# DDR3_ZET6.net
KiCad netlist of a schematic drawn in Altium Designer
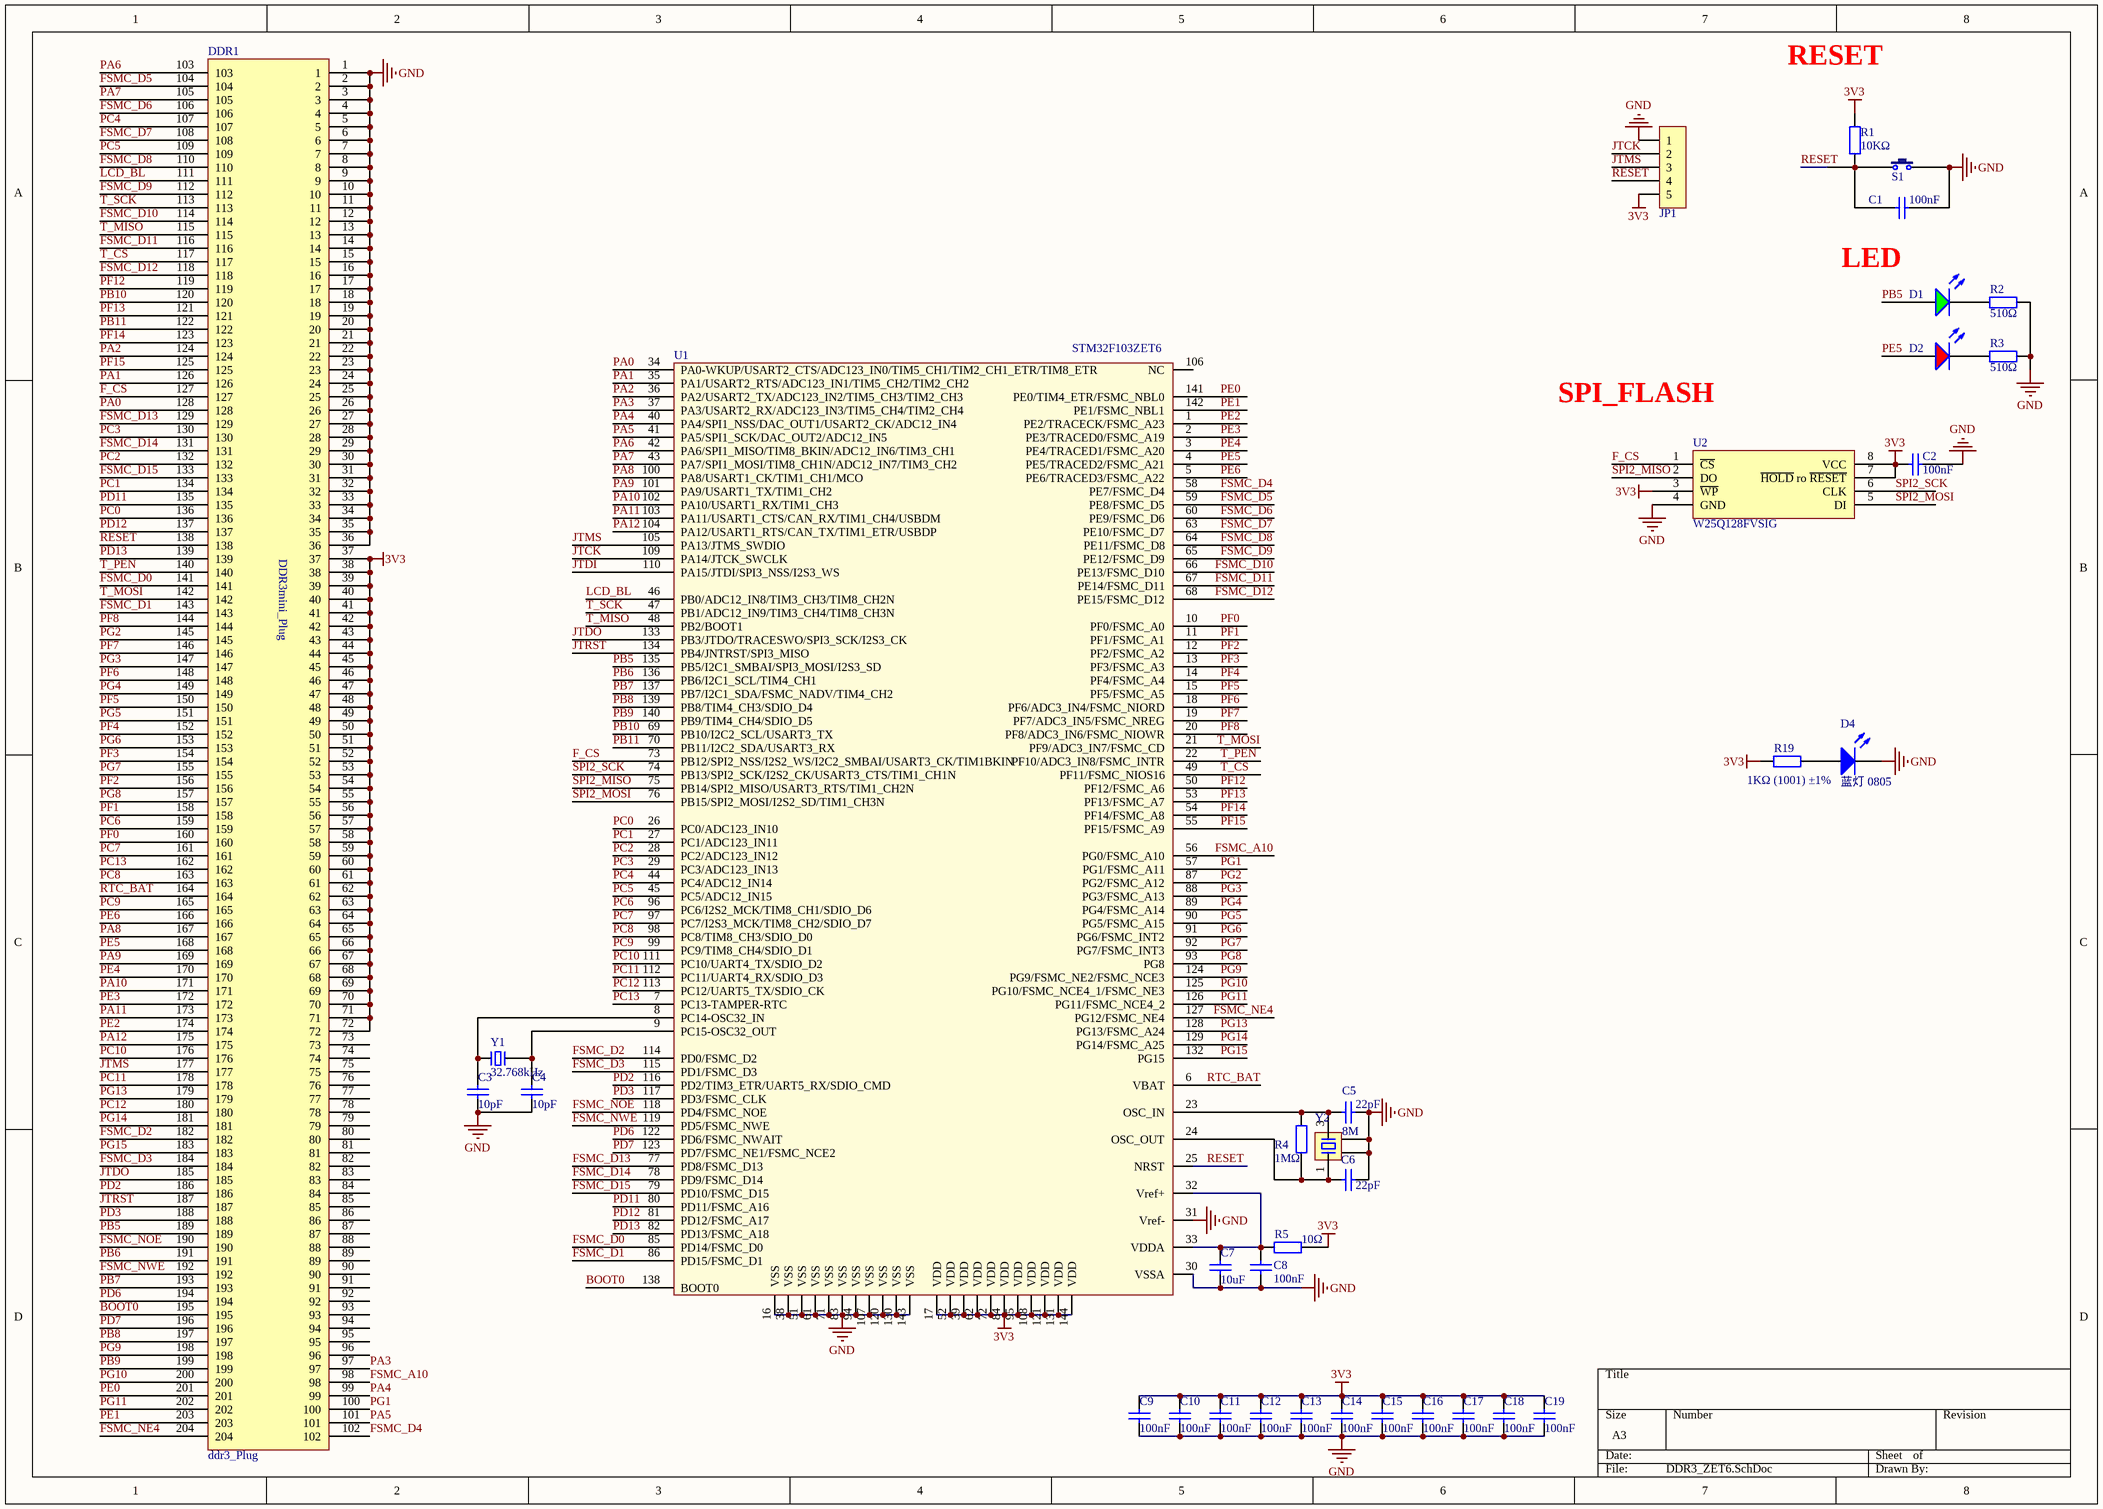
[diagram p0: DDR3_ZET6.SchDoc]

(export (version "E")
  (design (tool "Eeschema 10.0.6"))
  (components
    (comp (ref "C1")
      (value "100nF")
      (footprint "LC-0805_C")
      (description "贴片电容")
      (libsource (lib "Miscellaneous Devices LC") (part "0805 100nF(104) 10% 50V"))
    )
    (comp (ref "C2")
      (value "100nF")
      (footprint "LC-0805_C")
      (description "贴片电容")
      (libsource (lib "Miscellaneous Devices LC") (part "0805 100nF(104) 10% 50V"))
    )
    (comp (ref "C3")
      (value "10pF")
      (footprint "LC-0805_C")
      (description "贴片电容")
      (libsource (lib "Miscellaneous Devices LC") (part "0805 10pF (100) 5% 50V"))
    )
    (comp (ref "C4")
      (value "10pF")
      (footprint "LC-0805_C")
      (description "贴片电容")
      (libsource (lib "Miscellaneous Devices LC") (part "0805 10pF (100) 5% 50V"))
    )
    (comp (ref "C5")
      (value "22pF")
      (footprint "LC-0805_C")
      (description "贴片电容")
      (libsource (lib "Miscellaneous Devices LC") (part "0805 22pF (220) 5% 50V"))
    )
    (comp (ref "C6")
      (value "22pF")
      (footprint "LC-0805_C")
      (description "贴片电容")
      (libsource (lib "Miscellaneous Devices LC") (part "0805 22pF (220) 5% 50V"))
    )
    (comp (ref "C7")
      (value "10uF")
      (footprint "LC-0805_C")
      (description "贴片电容")
      (libsource (lib "Miscellaneous Devices LC") (part "0805 10uF (106) 10% 25V"))
    )
    (comp (ref "C8")
      (value "100nF")
      (footprint "LC-0805_C")
      (description "贴片电容")
      (libsource (lib "Miscellaneous Devices LC") (part "0805 100nF(104) 10% 50V"))
    )
    (comp (ref "C9")
      (value "100nF")
      (footprint "LC-0805_C")
      (description "贴片电容")
      (libsource (lib "Miscellaneous Devices LC") (part "0805 100nF(104) 10% 50V"))
    )
    (comp (ref "C10")
      (value "100nF")
      (footprint "LC-0805_C")
      (description "贴片电容")
      (libsource (lib "Miscellaneous Devices LC") (part "0805 100nF(104) 10% 50V"))
    )
    (comp (ref "C11")
      (value "100nF")
      (footprint "LC-0805_C")
      (description "贴片电容")
      (libsource (lib "Miscellaneous Devices LC") (part "0805 100nF(104) 10% 50V"))
    )
    (comp (ref "C12")
      (value "100nF")
      (footprint "LC-0805_C")
      (description "贴片电容")
      (libsource (lib "Miscellaneous Devices LC") (part "0805 100nF(104) 10% 50V"))
    )
    (comp (ref "C13")
      (value "100nF")
      (footprint "LC-0805_C")
      (description "贴片电容")
      (libsource (lib "Miscellaneous Devices LC") (part "0805 100nF(104) 10% 50V"))
    )
    (comp (ref "C14")
      (value "100nF")
      (footprint "LC-0805_C")
      (description "贴片电容")
      (libsource (lib "Miscellaneous Devices LC") (part "0805 100nF(104) 10% 50V"))
    )
    (comp (ref "C15")
      (value "100nF")
      (footprint "LC-0805_C")
      (description "贴片电容")
      (libsource (lib "Miscellaneous Devices LC") (part "0805 100nF(104) 10% 50V"))
    )
    (comp (ref "C16")
      (value "100nF")
      (footprint "LC-0805_C")
      (description "贴片电容")
      (libsource (lib "Miscellaneous Devices LC") (part "0805 100nF(104) 10% 50V"))
    )
    (comp (ref "C17")
      (value "100nF")
      (footprint "LC-0805_C")
      (description "贴片电容")
      (libsource (lib "Miscellaneous Devices LC") (part "0805 100nF(104) 10% 50V"))
    )
    (comp (ref "C18")
      (value "100nF")
      (footprint "LC-0805_C")
      (description "贴片电容")
      (libsource (lib "Miscellaneous Devices LC") (part "0805 100nF(104) 10% 50V"))
    )
    (comp (ref "C19")
      (value "100nF")
      (footprint "LC-0805_C")
      (description "贴片电容")
      (libsource (lib "Miscellaneous Devices LC") (part "0805 100nF(104) 10% 50V"))
    )
    (comp (ref "D1")
      (value "翠绿 0805")
      (footprint "LC-0805_LED_S1")
      (description "发光二极管")
      (libsource (lib "Miscellaneous Devices LC") (part "0805 翠绿"))
    )
    (comp (ref "D2")
      (value "红灯 0805")
      (footprint "LC-0805_LED_S1")
      (description "发光二极管")
      (libsource (lib "Miscellaneous Devices LC") (part "0805 红灯"))
    )
    (comp (ref "D4")
      (value "蓝灯 0805")
      (footprint "LC-0805_LED_S1")
      (description "发光二极管")
      (libsource (lib "Miscellaneous Devices LC") (part "0805 蓝灯"))
    )
    (comp (ref "DDR1")
      (value "ddr3_Plug")
      (footprint "DDR3_PLUG_LTE")
      (libsource (lib "my_lib") (part "ddr3_Plug"))
    )
    (comp (ref "JP1")
      (value "HDR-1X5")
      (footprint "HDR-1X5")
      (description "5P接插件")
      (fields (field (name "版权归属") "黎明电子style"))
      (libsource (lib "接插件") (part "Header 5"))
    )
    (comp (ref "R1")
      (value "10KΩ")
      (footprint "LC-0805_R")
      (description "贴片电阻")
      (libsource (lib "Miscellaneous Devices LC") (part "0805 10KΩ (1002) 1%"))
    )
    (comp (ref "R2")
      (value "510Ω")
      (footprint "LC-0805_R")
      (description "贴片电阻")
      (libsource (lib "Miscellaneous Devices LC") (part "0805 510Ω (5100) 1%"))
    )
    (comp (ref "R3")
      (value "510Ω")
      (footprint "LC-0805_R")
      (description "贴片电阻")
      (libsource (lib "Miscellaneous Devices LC") (part "0805 510Ω (5100) 1%"))
    )
    (comp (ref "R4")
      (value "1MΩ")
      (footprint "LC-0805_R")
      (description "贴片电阻")
      (libsource (lib "Miscellaneous Devices LC") (part "0805 1MΩ (1004) 1%"))
    )
    (comp (ref "R5")
      (value "10Ω")
      (footprint "LC-0805_R")
      (description "贴片电阻")
      (libsource (lib "Miscellaneous Devices LC") (part "0805 10Ω (10R0) 1%"))
    )
    (comp (ref "R19")
      (value "1KΩ (1001) ±1%")
      (footprint "LC-0805_R")
      (description "贴片电阻")
      (libsource (lib "Miscellaneous Devices LC") (part "0805 1KΩ (1001) 1%"))
    )
    (comp (ref "S1")
      (value "RESET")
      (footprint "TSW SMD-3*6*2.5")
      (description "3x6轻触开关")
      (fields (field (name "版权归属") "黎明电子style"))
      (libsource (lib "按键-开关") (part "TSW 3x6"))
    )
    (comp (ref "U1")
      (value "STM32F103ZET6")
      (footprint "LC-LQFP-144_20x20x05P")
      (libsource (lib "WarShip V3 STM32103封装库") (part "STM32F103ZET6"))
    )
    (comp (ref "U2")
      (value "W25Q128FVSIG")
      (footprint "LC-SOIC-8_208mil")
      (description "Flash ROM")
      (libsource (lib "Miscellaneous Devices LC") (part "W25Q128FVSIG"))
    )
    (comp (ref "Y1")
      (value "32.768kHz")
      (footprint "XTAL-3215")
      (description "2脚晶振")
      (fields (field (name "版权归属") "黎明电子style"))
      (libsource (lib "保险丝-晶振") (part "XTAL-2"))
    )
    (comp (ref "Y2")
      (value "8M")
      (footprint "XTAL-3225")
      (description "4脚晶振")
      (fields (field (name "版权归属") "黎明电子style"))
      (libsource (lib "保险丝-晶振") (part "XTAL-4"))
    )
  )
  (nets
    (net (code "1") (name "/BOOT0") (class "Default")
      (node (ref "DDR1") (pin "195") (pinfunction "195_195") (pintype "passive"))
      (node (ref "U1") (pin "138") (pinfunction "BOOT0_138") (pintype "passive"))
    )
    (net (code "2") (name "/FSMC_A10") (class "Default")
      (node (ref "DDR1") (pin "98") (pinfunction "98_98") (pintype "passive"))
      (node (ref "U1") (pin "56") (pinfunction "PG0/FSMC_A10_56") (pintype "passive"))
    )
    (net (code "3") (name "/FSMC_D0") (class "Default")
      (node (ref "DDR1") (pin "141") (pinfunction "141_141") (pintype "passive"))
      (node (ref "U1") (pin "85") (pinfunction "PD14/FSMC_D0_85") (pintype "passive"))
    )
    (net (code "4") (name "/FSMC_D1") (class "Default")
      (node (ref "DDR1") (pin "143") (pinfunction "143_143") (pintype "passive"))
      (node (ref "U1") (pin "86") (pinfunction "PD15/FSMC_D1_86") (pintype "passive"))
    )
    (net (code "5") (name "/FSMC_D2") (class "Default")
      (node (ref "DDR1") (pin "182") (pinfunction "182_182") (pintype "passive"))
      (node (ref "U1") (pin "114") (pinfunction "PD0/FSMC_D2_114") (pintype "passive"))
    )
    (net (code "6") (name "/FSMC_D3") (class "Default")
      (node (ref "DDR1") (pin "184") (pinfunction "184_184") (pintype "passive"))
      (node (ref "U1") (pin "115") (pinfunction "PD1/FSMC_D3_115") (pintype "passive"))
    )
    (net (code "7") (name "/FSMC_D4") (class "Default")
      (node (ref "DDR1") (pin "102") (pinfunction "102_102") (pintype "passive"))
      (node (ref "U1") (pin "58") (pinfunction "PE7/FSMC_D4_58") (pintype "passive"))
    )
    (net (code "8") (name "/FSMC_D5") (class "Default")
      (node (ref "DDR1") (pin "104") (pinfunction "104_104") (pintype "passive"))
      (node (ref "U1") (pin "59") (pinfunction "PE8/FSMC_D5_59") (pintype "passive"))
    )
    (net (code "9") (name "/FSMC_D6") (class "Default")
      (node (ref "DDR1") (pin "106") (pinfunction "106_106") (pintype "passive"))
      (node (ref "U1") (pin "60") (pinfunction "PE9/FSMC_D6_60") (pintype "passive"))
    )
    (net (code "10") (name "/FSMC_D7") (class "Default")
      (node (ref "DDR1") (pin "108") (pinfunction "108_108") (pintype "passive"))
      (node (ref "U1") (pin "63") (pinfunction "PE10/FSMC_D7_63") (pintype "passive"))
    )
    (net (code "11") (name "/FSMC_D8") (class "Default")
      (node (ref "DDR1") (pin "110") (pinfunction "110_110") (pintype "passive"))
      (node (ref "U1") (pin "64") (pinfunction "PE11/FSMC_D8_64") (pintype "passive"))
    )
    (net (code "12") (name "/FSMC_D9") (class "Default")
      (node (ref "DDR1") (pin "112") (pinfunction "112_112") (pintype "passive"))
      (node (ref "U1") (pin "65") (pinfunction "PE12/FSMC_D9_65") (pintype "passive"))
    )
    (net (code "13") (name "/FSMC_D10") (class "Default")
      (node (ref "DDR1") (pin "114") (pinfunction "114_114") (pintype "passive"))
      (node (ref "U1") (pin "66") (pinfunction "PE13/FSMC_D10_66") (pintype "passive"))
    )
    (net (code "14") (name "/FSMC_D11") (class "Default")
      (node (ref "DDR1") (pin "116") (pinfunction "116_116") (pintype "passive"))
      (node (ref "U1") (pin "67") (pinfunction "PE14/FSMC_D11_67") (pintype "passive"))
    )
    (net (code "15") (name "/FSMC_D12") (class "Default")
      (node (ref "DDR1") (pin "118") (pinfunction "118_118") (pintype "passive"))
      (node (ref "U1") (pin "68") (pinfunction "PE15/FSMC_D12_68") (pintype "passive"))
    )
    (net (code "16") (name "/FSMC_D13") (class "Default")
      (node (ref "DDR1") (pin "129") (pinfunction "129_129") (pintype "passive"))
      (node (ref "U1") (pin "77") (pinfunction "PD8/FSMC_D13_77") (pintype "passive"))
    )
    (net (code "17") (name "/FSMC_D14") (class "Default")
      (node (ref "DDR1") (pin "131") (pinfunction "131_131") (pintype "passive"))
      (node (ref "U1") (pin "78") (pinfunction "PD9/FSMC_D14_78") (pintype "passive"))
    )
    (net (code "18") (name "/FSMC_D15") (class "Default")
      (node (ref "DDR1") (pin "133") (pinfunction "133_133") (pintype "passive"))
      (node (ref "U1") (pin "79") (pinfunction "PD10/FSMC_D15_79") (pintype "passive"))
    )
    (net (code "19") (name "/FSMC_NE4") (class "Default")
      (node (ref "DDR1") (pin "204") (pinfunction "204_204") (pintype "passive"))
      (node (ref "U1") (pin "127") (pinfunction "PG12/FSMC_NE4_127") (pintype "passive"))
    )
    (net (code "20") (name "/FSMC_NOE") (class "Default")
      (node (ref "DDR1") (pin "190") (pinfunction "190_190") (pintype "passive"))
      (node (ref "U1") (pin "118") (pinfunction "PD4/FSMC_NOE_118") (pintype "passive"))
    )
    (net (code "21") (name "/FSMC_NWE") (class "Default")
      (node (ref "DDR1") (pin "192") (pinfunction "192_192") (pintype "passive"))
      (node (ref "U1") (pin "119") (pinfunction "PD5/FSMC_NWE_119") (pintype "passive"))
    )
    (net (code "22") (name "/F_CS") (class "Default")
      (node (ref "DDR1") (pin "127") (pinfunction "127_127") (pintype "passive"))
      (node (ref "U1") (pin "73") (pinfunction "PB12/SPI2_NSS/I2S2_WS/I2C2_SMBAI/USART3_CK/TIM1BKIN_73") (pintype "passive"))
      (node (ref "U2") (pin "1") (pinfunction "~{CS}_1") (pintype "passive"))
    )
    (net (code "23") (name "/JTCK") (class "Default")
      (node (ref "JP1") (pin "2") (pinfunction "2_2") (pintype "passive"))
      (node (ref "U1") (pin "109") (pinfunction "PA14/JTCK_SWCLK_109") (pintype "passive"))
    )
    (net (code "24") (name "/JTDI") (class "Default")
      (node (ref "U1") (pin "110") (pinfunction "PA15/JTDI/SPI3_NSS/I2S3_WS_110") (pintype "passive"))
    )
    (net (code "25") (name "/JTDO") (class "Default")
      (node (ref "DDR1") (pin "185") (pinfunction "185_185") (pintype "passive"))
      (node (ref "U1") (pin "133") (pinfunction "PB3/JTDO/TRACESWO/SPI3_SCK/I2S3_CK_133") (pintype "passive"))
    )
    (net (code "26") (name "/JTMS") (class "Default")
      (node (ref "DDR1") (pin "177") (pinfunction "177_177") (pintype "passive"))
      (node (ref "JP1") (pin "3") (pinfunction "3_3") (pintype "passive"))
      (node (ref "U1") (pin "105") (pinfunction "PA13/JTMS_SWDIO_105") (pintype "passive"))
    )
    (net (code "27") (name "/JTRST") (class "Default")
      (node (ref "DDR1") (pin "187") (pinfunction "187_187") (pintype "passive"))
      (node (ref "U1") (pin "134") (pinfunction "PB4/JNTRST/SPI3_MISO_134") (pintype "passive"))
    )
    (net (code "28") (name "/LCD_BL") (class "Default")
      (node (ref "DDR1") (pin "111") (pinfunction "111_111") (pintype "passive"))
      (node (ref "U1") (pin "46") (pinfunction "PB0/ADC12_IN8/TIM3_CH3/TIM8_CH2N_46") (pintype "passive"))
    )
    (net (code "29") (name "/PA0") (class "Default")
      (node (ref "DDR1") (pin "128") (pinfunction "128_128") (pintype "passive"))
      (node (ref "U1") (pin "34") (pinfunction "PA0-WKUP/USART2_CTS/ADC123_IN0/TIM5_CH1/TIM2_CH1_ETR/TIM8_ETR_34") (pintype "passive"))
    )
    (net (code "30") (name "/PA1") (class "Default")
      (node (ref "DDR1") (pin "126") (pinfunction "126_126") (pintype "passive"))
      (node (ref "U1") (pin "35") (pinfunction "PA1/USART2_RTS/ADC123_IN1/TIM5_CH2/TIM2_CH2_35") (pintype "passive"))
    )
    (net (code "31") (name "/PA2") (class "Default")
      (node (ref "DDR1") (pin "124") (pinfunction "124_124") (pintype "passive"))
      (node (ref "U1") (pin "36") (pinfunction "PA2/USART2_TX/ADC123_IN2/TIM5_CH3/TIM2_CH3_36") (pintype "passive"))
    )
    (net (code "32") (name "/PA3") (class "Default")
      (node (ref "DDR1") (pin "97") (pinfunction "97_97") (pintype "passive"))
      (node (ref "U1") (pin "37") (pinfunction "PA3/USART2_RX/ADC123_IN3/TIM5_CH4/TIM2_CH4_37") (pintype "passive"))
    )
    (net (code "33") (name "/PA4") (class "Default")
      (node (ref "DDR1") (pin "99") (pinfunction "99_99") (pintype "passive"))
      (node (ref "U1") (pin "40") (pinfunction "PA4/SPI1_NSS/DAC_OUT1/USART2_CK/ADC12_IN4_40") (pintype "passive"))
    )
    (net (code "34") (name "/PA5") (class "Default")
      (node (ref "DDR1") (pin "101") (pinfunction "101_101") (pintype "passive"))
      (node (ref "U1") (pin "41") (pinfunction "PA5/SPI1_SCK/DAC_OUT2/ADC12_IN5_41") (pintype "passive"))
    )
    (net (code "35") (name "/PA6") (class "Default")
      (node (ref "DDR1") (pin "103") (pinfunction "103_103") (pintype "passive"))
      (node (ref "U1") (pin "42") (pinfunction "PA6/SPI1_MISO/TIM8_BKIN/ADC12_IN6/TIM3_CH1_42") (pintype "passive"))
    )
    (net (code "36") (name "/PA7") (class "Default")
      (node (ref "DDR1") (pin "105") (pinfunction "105_105") (pintype "passive"))
      (node (ref "U1") (pin "43") (pinfunction "PA7/SPI1_MOSI/TIM8_CH1N/ADC12_IN7/TIM3_CH2_43") (pintype "passive"))
    )
    (net (code "37") (name "/PA8") (class "Default")
      (node (ref "DDR1") (pin "167") (pinfunction "167_167") (pintype "passive"))
      (node (ref "U1") (pin "100") (pinfunction "PA8/USART1_CK/TIM1_CH1/MCO_100") (pintype "passive"))
    )
    (net (code "38") (name "/PA9") (class "Default")
      (node (ref "DDR1") (pin "169") (pinfunction "169_169") (pintype "passive"))
      (node (ref "U1") (pin "101") (pinfunction "PA9/USART1_TX/TIM1_CH2_101") (pintype "passive"))
    )
    (net (code "39") (name "/PA10") (class "Default")
      (node (ref "DDR1") (pin "171") (pinfunction "171_171") (pintype "passive"))
      (node (ref "U1") (pin "102") (pinfunction "PA10/USART1_RX/TIM1_CH3_102") (pintype "passive"))
    )
    (net (code "40") (name "/PA11") (class "Default")
      (node (ref "DDR1") (pin "173") (pinfunction "173_173") (pintype "passive"))
      (node (ref "U1") (pin "103") (pinfunction "PA11/USART1_CTS/CAN_RX/TIM1_CH4/USBDM_103") (pintype "passive"))
    )
    (net (code "41") (name "/PA12") (class "Default")
      (node (ref "DDR1") (pin "175") (pinfunction "175_175") (pintype "passive"))
      (node (ref "U1") (pin "104") (pinfunction "PA12/USART1_RTS/CAN_TX/TIM1_ETR/USBDP_104") (pintype "passive"))
    )
    (net (code "42") (name "/PB5") (class "Default")
      (node (ref "D1") (pin "A") (pinfunction "A_A") (pintype "passive"))
      (node (ref "DDR1") (pin "189") (pinfunction "189_189") (pintype "passive"))
      (node (ref "U1") (pin "135") (pinfunction "PB5/I2C1_SMBAI/SPI3_MOSI/I2S3_SD_135") (pintype "passive"))
    )
    (net (code "43") (name "/PB6") (class "Default")
      (node (ref "DDR1") (pin "191") (pinfunction "191_191") (pintype "passive"))
      (node (ref "U1") (pin "136") (pinfunction "PB6/I2C1_SCL/TIM4_CH1_136") (pintype "passive"))
    )
    (net (code "44") (name "/PB7") (class "Default")
      (node (ref "DDR1") (pin "193") (pinfunction "193_193") (pintype "passive"))
      (node (ref "U1") (pin "137") (pinfunction "PB7/I2C1_SDA/FSMC_NADV/TIM4_CH2_137") (pintype "passive"))
    )
    (net (code "45") (name "/PB8") (class "Default")
      (node (ref "DDR1") (pin "197") (pinfunction "197_197") (pintype "passive"))
      (node (ref "U1") (pin "139") (pinfunction "PB8/TIM4_CH3/SDIO_D4_139") (pintype "passive"))
    )
    (net (code "46") (name "/PB9") (class "Default")
      (node (ref "DDR1") (pin "199") (pinfunction "199_199") (pintype "passive"))
      (node (ref "U1") (pin "140") (pinfunction "PB9/TIM4_CH4/SDIO_D5_140") (pintype "passive"))
    )
    (net (code "47") (name "/PB10") (class "Default")
      (node (ref "DDR1") (pin "120") (pinfunction "120_120") (pintype "passive"))
      (node (ref "U1") (pin "69") (pinfunction "PB10/I2C2_SCL/USART3_TX_69") (pintype "passive"))
    )
    (net (code "48") (name "/PB11") (class "Default")
      (node (ref "DDR1") (pin "122") (pinfunction "122_122") (pintype "passive"))
      (node (ref "U1") (pin "70") (pinfunction "PB11/I2C2_SDA/USART3_RX_70") (pintype "passive"))
    )
    (net (code "49") (name "/PC0") (class "Default")
      (node (ref "DDR1") (pin "136") (pinfunction "136_136") (pintype "passive"))
      (node (ref "U1") (pin "26") (pinfunction "PC0/ADC123_IN10_26") (pintype "passive"))
    )
    (net (code "50") (name "/PC1") (class "Default")
      (node (ref "DDR1") (pin "134") (pinfunction "134_134") (pintype "passive"))
      (node (ref "U1") (pin "27") (pinfunction "PC1/ADC123_IN11_27") (pintype "passive"))
    )
    (net (code "51") (name "/PC2") (class "Default")
      (node (ref "DDR1") (pin "132") (pinfunction "132_132") (pintype "passive"))
      (node (ref "U1") (pin "28") (pinfunction "PC2/ADC123_IN12_28") (pintype "passive"))
    )
    (net (code "52") (name "/PC3") (class "Default")
      (node (ref "DDR1") (pin "130") (pinfunction "130_130") (pintype "passive"))
      (node (ref "U1") (pin "29") (pinfunction "PC3/ADC123_IN13_29") (pintype "passive"))
    )
    (net (code "53") (name "/PC4") (class "Default")
      (node (ref "DDR1") (pin "107") (pinfunction "107_107") (pintype "passive"))
      (node (ref "U1") (pin "44") (pinfunction "PC4/ADC12_IN14_44") (pintype "passive"))
    )
    (net (code "54") (name "/PC5") (class "Default")
      (node (ref "DDR1") (pin "109") (pinfunction "109_109") (pintype "passive"))
      (node (ref "U1") (pin "45") (pinfunction "PC5/ADC12_IN15_45") (pintype "passive"))
    )
    (net (code "55") (name "/PC6") (class "Default")
      (node (ref "DDR1") (pin "159") (pinfunction "159_159") (pintype "passive"))
      (node (ref "U1") (pin "96") (pinfunction "PC6/I2S2_MCK/TIM8_CH1/SDIO_D6_96") (pintype "passive"))
    )
    (net (code "56") (name "/PC7") (class "Default")
      (node (ref "DDR1") (pin "161") (pinfunction "161_161") (pintype "passive"))
      (node (ref "U1") (pin "97") (pinfunction "PC7/I2S3_MCK/TIM8_CH2/SDIO_D7_97") (pintype "passive"))
    )
    (net (code "57") (name "/PC8") (class "Default")
      (node (ref "DDR1") (pin "163") (pinfunction "163_163") (pintype "passive"))
      (node (ref "U1") (pin "98") (pinfunction "PC8/TIM8_CH3/SDIO_D0_98") (pintype "passive"))
    )
    (net (code "58") (name "/PC9") (class "Default")
      (node (ref "DDR1") (pin "165") (pinfunction "165_165") (pintype "passive"))
      (node (ref "U1") (pin "99") (pinfunction "PC9/TIM8_CH4/SDIO_D1_99") (pintype "passive"))
    )
    (net (code "59") (name "/PC10") (class "Default")
      (node (ref "DDR1") (pin "176") (pinfunction "176_176") (pintype "passive"))
      (node (ref "U1") (pin "111") (pinfunction "PC10/UART4_TX/SDIO_D2_111") (pintype "passive"))
    )
    (net (code "60") (name "/PC11") (class "Default")
      (node (ref "DDR1") (pin "178") (pinfunction "178_178") (pintype "passive"))
      (node (ref "U1") (pin "112") (pinfunction "PC11/UART4_RX/SDIO_D3_112") (pintype "passive"))
    )
    (net (code "61") (name "/PC12") (class "Default")
      (node (ref "DDR1") (pin "180") (pinfunction "180_180") (pintype "passive"))
      (node (ref "U1") (pin "113") (pinfunction "PC12/UART5_TX/SDIO_CK_113") (pintype "passive"))
    )
    (net (code "62") (name "/PC13") (class "Default")
      (node (ref "DDR1") (pin "162") (pinfunction "162_162") (pintype "passive"))
      (node (ref "U1") (pin "7") (pinfunction "PC13-TAMPER-RTC_7") (pintype "passive"))
    )
    (net (code "63") (name "/PD2") (class "Default")
      (node (ref "DDR1") (pin "186") (pinfunction "186_186") (pintype "passive"))
      (node (ref "U1") (pin "116") (pinfunction "PD2/TIM3_ETR/UART5_RX/SDIO_CMD_116") (pintype "passive"))
    )
    (net (code "64") (name "/PD3") (class "Default")
      (node (ref "DDR1") (pin "188") (pinfunction "188_188") (pintype "passive"))
      (node (ref "U1") (pin "117") (pinfunction "PD3/FSMC_CLK_117") (pintype "passive"))
    )
    (net (code "65") (name "/PD6") (class "Default")
      (node (ref "DDR1") (pin "194") (pinfunction "194_194") (pintype "passive"))
      (node (ref "U1") (pin "122") (pinfunction "PD6/FSMC_NWAIT_122") (pintype "passive"))
    )
    (net (code "66") (name "/PD7") (class "Default")
      (node (ref "DDR1") (pin "196") (pinfunction "196_196") (pintype "passive"))
      (node (ref "U1") (pin "123") (pinfunction "PD7/FSMC_NE1/FSMC_NCE2_123") (pintype "passive"))
    )
    (net (code "67") (name "/PD11") (class "Default")
      (node (ref "DDR1") (pin "135") (pinfunction "135_135") (pintype "passive"))
      (node (ref "U1") (pin "80") (pinfunction "PD11/FSMC_A16_80") (pintype "passive"))
    )
    (net (code "68") (name "/PD12") (class "Default")
      (node (ref "DDR1") (pin "137") (pinfunction "137_137") (pintype "passive"))
      (node (ref "U1") (pin "81") (pinfunction "PD12/FSMC_A17_81") (pintype "passive"))
    )
    (net (code "69") (name "/PD13") (class "Default")
      (node (ref "DDR1") (pin "139") (pinfunction "139_139") (pintype "passive"))
      (node (ref "U1") (pin "82") (pinfunction "PD13/FSMC_A18_82") (pintype "passive"))
    )
    (net (code "70") (name "/PE0") (class "Default")
      (node (ref "DDR1") (pin "201") (pinfunction "201_201") (pintype "passive"))
      (node (ref "U1") (pin "141") (pinfunction "PE0/TIM4_ETR/FSMC_NBL0_141") (pintype "passive"))
    )
    (net (code "71") (name "/PE1") (class "Default")
      (node (ref "DDR1") (pin "203") (pinfunction "203_203") (pintype "passive"))
      (node (ref "U1") (pin "142") (pinfunction "PE1/FSMC_NBL1_142") (pintype "passive"))
    )
    (net (code "72") (name "/PE2") (class "Default")
      (node (ref "DDR1") (pin "174") (pinfunction "174_174") (pintype "passive"))
      (node (ref "U1") (pin "1") (pinfunction "PE2/TRACECK/FSMC_A23_1") (pintype "passive"))
    )
    (net (code "73") (name "/PE3") (class "Default")
      (node (ref "DDR1") (pin "172") (pinfunction "172_172") (pintype "passive"))
      (node (ref "U1") (pin "2") (pinfunction "PE3/TRACED0/FSMC_A19_2") (pintype "passive"))
    )
    (net (code "74") (name "/PE4") (class "Default")
      (node (ref "DDR1") (pin "170") (pinfunction "170_170") (pintype "passive"))
      (node (ref "U1") (pin "3") (pinfunction "PE4/TRACED1/FSMC_A20_3") (pintype "passive"))
    )
    (net (code "75") (name "/PE5") (class "Default")
      (node (ref "D2") (pin "A") (pinfunction "A_A") (pintype "passive"))
      (node (ref "DDR1") (pin "168") (pinfunction "168_168") (pintype "passive"))
      (node (ref "U1") (pin "4") (pinfunction "PE5/TRACED2/FSMC_A21_4") (pintype "passive"))
    )
    (net (code "76") (name "/PE6") (class "Default")
      (node (ref "DDR1") (pin "166") (pinfunction "166_166") (pintype "passive"))
      (node (ref "U1") (pin "5") (pinfunction "PE6/TRACED3/FSMC_A22_5") (pintype "passive"))
    )
    (net (code "77") (name "/PF0") (class "Default")
      (node (ref "DDR1") (pin "160") (pinfunction "160_160") (pintype "passive"))
      (node (ref "U1") (pin "10") (pinfunction "PF0/FSMC_A0_10") (pintype "passive"))
    )
    (net (code "78") (name "/PF1") (class "Default")
      (node (ref "DDR1") (pin "158") (pinfunction "158_158") (pintype "passive"))
      (node (ref "U1") (pin "11") (pinfunction "PF1/FSMC_A1_11") (pintype "passive"))
    )
    (net (code "79") (name "/PF2") (class "Default")
      (node (ref "DDR1") (pin "156") (pinfunction "156_156") (pintype "passive"))
      (node (ref "U1") (pin "12") (pinfunction "PF2/FSMC_A2_12") (pintype "passive"))
    )
    (net (code "80") (name "/PF3") (class "Default")
      (node (ref "DDR1") (pin "154") (pinfunction "154_154") (pintype "passive"))
      (node (ref "U1") (pin "13") (pinfunction "PF3/FSMC_A3_13") (pintype "passive"))
    )
    (net (code "81") (name "/PF4") (class "Default")
      (node (ref "DDR1") (pin "152") (pinfunction "152_152") (pintype "passive"))
      (node (ref "U1") (pin "14") (pinfunction "PF4/FSMC_A4_14") (pintype "passive"))
    )
    (net (code "82") (name "/PF5") (class "Default")
      (node (ref "DDR1") (pin "150") (pinfunction "150_150") (pintype "passive"))
      (node (ref "U1") (pin "15") (pinfunction "PF5/FSMC_A5_15") (pintype "passive"))
    )
    (net (code "83") (name "/PF6") (class "Default")
      (node (ref "DDR1") (pin "148") (pinfunction "148_148") (pintype "passive"))
      (node (ref "U1") (pin "18") (pinfunction "PF6/ADC3_IN4/FSMC_NIORD_18") (pintype "passive"))
    )
    (net (code "84") (name "/PF7") (class "Default")
      (node (ref "DDR1") (pin "146") (pinfunction "146_146") (pintype "passive"))
      (node (ref "U1") (pin "19") (pinfunction "PF7/ADC3_IN5/FSMC_NREG_19") (pintype "passive"))
    )
    (net (code "85") (name "/PF8") (class "Default")
      (node (ref "DDR1") (pin "144") (pinfunction "144_144") (pintype "passive"))
      (node (ref "U1") (pin "20") (pinfunction "PF8/ADC3_IN6/FSMC_NIOWR_20") (pintype "passive"))
    )
    (net (code "86") (name "/PF12") (class "Default")
      (node (ref "DDR1") (pin "119") (pinfunction "119_119") (pintype "passive"))
      (node (ref "U1") (pin "50") (pinfunction "PF12/FSMC_A6_50") (pintype "passive"))
    )
    (net (code "87") (name "/PF13") (class "Default")
      (node (ref "DDR1") (pin "121") (pinfunction "121_121") (pintype "passive"))
      (node (ref "U1") (pin "53") (pinfunction "PF13/FSMC_A7_53") (pintype "passive"))
    )
    (net (code "88") (name "/PF14") (class "Default")
      (node (ref "DDR1") (pin "123") (pinfunction "123_123") (pintype "passive"))
      (node (ref "U1") (pin "54") (pinfunction "PF14/FSMC_A8_54") (pintype "passive"))
    )
    (net (code "89") (name "/PF15") (class "Default")
      (node (ref "DDR1") (pin "125") (pinfunction "125_125") (pintype "passive"))
      (node (ref "U1") (pin "55") (pinfunction "PF15/FSMC_A9_55") (pintype "passive"))
    )
    (net (code "90") (name "/PG1") (class "Default")
      (node (ref "DDR1") (pin "100") (pinfunction "100_100") (pintype "passive"))
      (node (ref "U1") (pin "57") (pinfunction "PG1/FSMC_A11_57") (pintype "passive"))
    )
    (net (code "91") (name "/PG2") (class "Default")
      (node (ref "DDR1") (pin "145") (pinfunction "145_145") (pintype "passive"))
      (node (ref "U1") (pin "87") (pinfunction "PG2/FSMC_A12_87") (pintype "passive"))
    )
    (net (code "92") (name "/PG3") (class "Default")
      (node (ref "DDR1") (pin "147") (pinfunction "147_147") (pintype "passive"))
      (node (ref "U1") (pin "88") (pinfunction "PG3/FSMC_A13_88") (pintype "passive"))
    )
    (net (code "93") (name "/PG4") (class "Default")
      (node (ref "DDR1") (pin "149") (pinfunction "149_149") (pintype "passive"))
      (node (ref "U1") (pin "89") (pinfunction "PG4/FSMC_A14_89") (pintype "passive"))
    )
    (net (code "94") (name "/PG5") (class "Default")
      (node (ref "DDR1") (pin "151") (pinfunction "151_151") (pintype "passive"))
      (node (ref "U1") (pin "90") (pinfunction "PG5/FSMC_A15_90") (pintype "passive"))
    )
    (net (code "95") (name "/PG6") (class "Default")
      (node (ref "DDR1") (pin "153") (pinfunction "153_153") (pintype "passive"))
      (node (ref "U1") (pin "91") (pinfunction "PG6/FSMC_INT2_91") (pintype "passive"))
    )
    (net (code "96") (name "/PG7") (class "Default")
      (node (ref "DDR1") (pin "155") (pinfunction "155_155") (pintype "passive"))
      (node (ref "U1") (pin "92") (pinfunction "PG7/FSMC_INT3_92") (pintype "passive"))
    )
    (net (code "97") (name "/PG8") (class "Default")
      (node (ref "DDR1") (pin "157") (pinfunction "157_157") (pintype "passive"))
      (node (ref "U1") (pin "93") (pinfunction "PG8_93") (pintype "passive"))
    )
    (net (code "98") (name "/PG9") (class "Default")
      (node (ref "DDR1") (pin "198") (pinfunction "198_198") (pintype "passive"))
      (node (ref "U1") (pin "124") (pinfunction "PG9/FSMC_NE2/FSMC_NCE3_124") (pintype "passive"))
    )
    (net (code "99") (name "/PG10") (class "Default")
      (node (ref "DDR1") (pin "200") (pinfunction "200_200") (pintype "passive"))
      (node (ref "U1") (pin "125") (pinfunction "PG10/FSMC_NCE4_1/FSMC_NE3_125") (pintype "passive"))
    )
    (net (code "100") (name "/PG11") (class "Default")
      (node (ref "DDR1") (pin "202") (pinfunction "202_202") (pintype "passive"))
      (node (ref "U1") (pin "126") (pinfunction "PG11/FSMC_NCE4_2_126") (pintype "passive"))
    )
    (net (code "101") (name "/PG13") (class "Default")
      (node (ref "DDR1") (pin "179") (pinfunction "179_179") (pintype "passive"))
      (node (ref "U1") (pin "128") (pinfunction "PG13/FSMC_A24_128") (pintype "passive"))
    )
    (net (code "102") (name "/PG14") (class "Default")
      (node (ref "DDR1") (pin "181") (pinfunction "181_181") (pintype "passive"))
      (node (ref "U1") (pin "129") (pinfunction "PG14/FSMC_A25_129") (pintype "passive"))
    )
    (net (code "103") (name "/PG15") (class "Default")
      (node (ref "DDR1") (pin "183") (pinfunction "183_183") (pintype "passive"))
      (node (ref "U1") (pin "132") (pinfunction "PG15_132") (pintype "passive"))
    )
    (net (code "104") (name "/RESET") (class "Default")
      (node (ref "C1") (pin "1") (pinfunction "1_1") (pintype "passive"))
      (node (ref "DDR1") (pin "138") (pinfunction "138_138") (pintype "passive"))
      (node (ref "JP1") (pin "4") (pinfunction "4_4") (pintype "passive"))
      (node (ref "R1") (pin "1") (pinfunction "1_1") (pintype "passive"))
      (node (ref "S1") (pin "1") (pinfunction "1_1") (pintype "passive"))
      (node (ref "U1") (pin "25") (pinfunction "NRST_25") (pintype "passive"))
    )
    (net (code "105") (name "/RTC_BAT") (class "Default")
      (node (ref "DDR1") (pin "164") (pinfunction "164_164") (pintype "passive"))
      (node (ref "U1") (pin "6") (pinfunction "VBAT_6") (pintype "passive"))
    )
    (net (code "106") (name "/SPI2_MISO") (class "Default")
      (node (ref "U1") (pin "75") (pinfunction "PB14/SPI2_MISO/USART3_RTS/TIM1_CH2N_75") (pintype "passive"))
      (node (ref "U2") (pin "2") (pinfunction "DO_2") (pintype "passive"))
    )
    (net (code "107") (name "/SPI2_MOSI") (class "Default")
      (node (ref "U1") (pin "76") (pinfunction "PB15/SPI2_MOSI/I2S2_SD/TIM1_CH3N_76") (pintype "passive"))
      (node (ref "U2") (pin "5") (pinfunction "DI_5") (pintype "passive"))
    )
    (net (code "108") (name "/SPI2_SCK") (class "Default")
      (node (ref "U1") (pin "74") (pinfunction "PB13/SPI2_SCK/I2S2_CK/USART3_CTS/TIM1_CH1N_74") (pintype "passive"))
      (node (ref "U2") (pin "6") (pinfunction "CLK_6") (pintype "passive"))
    )
    (net (code "109") (name "/T_CS") (class "Default")
      (node (ref "DDR1") (pin "117") (pinfunction "117_117") (pintype "passive"))
      (node (ref "U1") (pin "49") (pinfunction "PF11/FSMC_NIOS16_49") (pintype "passive"))
    )
    (net (code "110") (name "/T_MISO") (class "Default")
      (node (ref "DDR1") (pin "115") (pinfunction "115_115") (pintype "passive"))
      (node (ref "U1") (pin "48") (pinfunction "PB2/BOOT1_48") (pintype "passive"))
    )
    (net (code "111") (name "/T_MOSI") (class "Default")
      (node (ref "DDR1") (pin "142") (pinfunction "142_142") (pintype "passive"))
      (node (ref "U1") (pin "21") (pinfunction "PF9/ADC3_IN7/FSMC_CD_21") (pintype "passive"))
    )
    (net (code "112") (name "/T_PEN") (class "Default")
      (node (ref "DDR1") (pin "140") (pinfunction "140_140") (pintype "passive"))
      (node (ref "U1") (pin "22") (pinfunction "PF10/ADC3_IN8/FSMC_INTR_22") (pintype "passive"))
    )
    (net (code "113") (name "/T_SCK") (class "Default")
      (node (ref "DDR1") (pin "113") (pinfunction "113_113") (pintype "passive"))
      (node (ref "U1") (pin "47") (pinfunction "PB1/ADC12_IN9/TIM3_CH4/TIM8_CH3N_47") (pintype "passive"))
    )
    (net (code "114") (name "3V3") (class "Default")
      (node (ref "C10") (pin "2") (pinfunction "2_2") (pintype "passive"))
      (node (ref "C11") (pin "2") (pinfunction "2_2") (pintype "passive"))
      (node (ref "C12") (pin "2") (pinfunction "2_2") (pintype "passive"))
      (node (ref "C13") (pin "2") (pinfunction "2_2") (pintype "passive"))
      (node (ref "C14") (pin "2") (pinfunction "2_2") (pintype "passive"))
      (node (ref "C15") (pin "2") (pinfunction "2_2") (pintype "passive"))
      (node (ref "C16") (pin "2") (pinfunction "2_2") (pintype "passive"))
      (node (ref "C17") (pin "2") (pinfunction "2_2") (pintype "passive"))
      (node (ref "C18") (pin "2") (pinfunction "2_2") (pintype "passive"))
      (node (ref "C19") (pin "2") (pinfunction "2_2") (pintype "passive"))
      (node (ref "C2") (pin "1") (pinfunction "1_1") (pintype "passive"))
      (node (ref "C9") (pin "2") (pinfunction "2_2") (pintype "passive"))
      (node (ref "DDR1") (pin "37") (pinfunction "37_37") (pintype "passive"))
      (node (ref "DDR1") (pin "38") (pinfunction "38_38") (pintype "passive"))
      (node (ref "DDR1") (pin "39") (pinfunction "39_39") (pintype "passive"))
      (node (ref "DDR1") (pin "40") (pinfunction "40_40") (pintype "passive"))
      (node (ref "DDR1") (pin "41") (pinfunction "41_41") (pintype "passive"))
      (node (ref "DDR1") (pin "42") (pinfunction "42_42") (pintype "passive"))
      (node (ref "DDR1") (pin "43") (pinfunction "43_43") (pintype "passive"))
      (node (ref "DDR1") (pin "44") (pinfunction "44_44") (pintype "passive"))
      (node (ref "DDR1") (pin "45") (pinfunction "45_45") (pintype "passive"))
      (node (ref "DDR1") (pin "46") (pinfunction "46_46") (pintype "passive"))
      (node (ref "DDR1") (pin "47") (pinfunction "47_47") (pintype "passive"))
      (node (ref "DDR1") (pin "48") (pinfunction "48_48") (pintype "passive"))
      (node (ref "DDR1") (pin "49") (pinfunction "49_49") (pintype "passive"))
      (node (ref "DDR1") (pin "50") (pinfunction "50_50") (pintype "passive"))
      (node (ref "DDR1") (pin "51") (pinfunction "51_51") (pintype "passive"))
      (node (ref "DDR1") (pin "52") (pinfunction "52_52") (pintype "passive"))
      (node (ref "DDR1") (pin "53") (pinfunction "53_53") (pintype "passive"))
      (node (ref "DDR1") (pin "54") (pinfunction "54_54") (pintype "passive"))
      (node (ref "DDR1") (pin "55") (pinfunction "55_55") (pintype "passive"))
      (node (ref "DDR1") (pin "56") (pinfunction "56_56") (pintype "passive"))
      (node (ref "DDR1") (pin "57") (pinfunction "57_57") (pintype "passive"))
      (node (ref "DDR1") (pin "58") (pinfunction "58_58") (pintype "passive"))
      (node (ref "DDR1") (pin "59") (pinfunction "59_59") (pintype "passive"))
      (node (ref "DDR1") (pin "60") (pinfunction "60_60") (pintype "passive"))
      (node (ref "DDR1") (pin "61") (pinfunction "61_61") (pintype "passive"))
      (node (ref "DDR1") (pin "62") (pinfunction "62_62") (pintype "passive"))
      (node (ref "DDR1") (pin "63") (pinfunction "63_63") (pintype "passive"))
      (node (ref "DDR1") (pin "64") (pinfunction "64_64") (pintype "passive"))
      (node (ref "DDR1") (pin "65") (pinfunction "65_65") (pintype "passive"))
      (node (ref "DDR1") (pin "66") (pinfunction "66_66") (pintype "passive"))
      (node (ref "DDR1") (pin "67") (pinfunction "67_67") (pintype "passive"))
      (node (ref "DDR1") (pin "68") (pinfunction "68_68") (pintype "passive"))
      (node (ref "DDR1") (pin "69") (pinfunction "69_69") (pintype "passive"))
      (node (ref "DDR1") (pin "70") (pinfunction "70_70") (pintype "passive"))
      (node (ref "DDR1") (pin "71") (pinfunction "71_71") (pintype "passive"))
      (node (ref "DDR1") (pin "72") (pinfunction "72_72") (pintype "passive"))
      (node (ref "JP1") (pin "5") (pinfunction "5_5") (pintype "passive"))
      (node (ref "R1") (pin "2") (pinfunction "2_2") (pintype "passive"))
      (node (ref "R19") (pin "1") (pinfunction "1_1") (pintype "passive"))
      (node (ref "R5") (pin "2") (pinfunction "2_2") (pintype "passive"))
      (node (ref "U1") (pin "108") (pinfunction "VDD_108") (pintype "passive"))
      (node (ref "U1") (pin "121") (pinfunction "VDD_121") (pintype "passive"))
      (node (ref "U1") (pin "131") (pinfunction "VDD_131") (pintype "passive"))
      (node (ref "U1") (pin "144") (pinfunction "VDD_144") (pintype "passive"))
      (node (ref "U1") (pin "17") (pinfunction "VDD_17") (pintype "passive"))
      (node (ref "U1") (pin "39") (pinfunction "VDD_39") (pintype "passive"))
      (node (ref "U1") (pin "52") (pinfunction "VDD_52") (pintype "passive"))
      (node (ref "U1") (pin "62") (pinfunction "VDD_62") (pintype "passive"))
      (node (ref "U1") (pin "72") (pinfunction "VDD_72") (pintype "passive"))
      (node (ref "U1") (pin "84") (pinfunction "VDD_84") (pintype "passive"))
      (node (ref "U1") (pin "95") (pinfunction "VDD_95") (pintype "passive"))
      (node (ref "U2") (pin "3") (pinfunction "~{WP}_3") (pintype "passive"))
      (node (ref "U2") (pin "7") (pinfunction "~{HOLD}_ro_~{RESET}_7") (pintype "passive"))
      (node (ref "U2") (pin "8") (pinfunction "VCC_8") (pintype "passive"))
    )
    (net (code "115") (name "GND") (class "Default")
      (node (ref "C1") (pin "2") (pinfunction "2_2") (pintype "passive"))
      (node (ref "C10") (pin "1") (pinfunction "1_1") (pintype "passive"))
      (node (ref "C11") (pin "1") (pinfunction "1_1") (pintype "passive"))
      (node (ref "C12") (pin "1") (pinfunction "1_1") (pintype "passive"))
      (node (ref "C13") (pin "1") (pinfunction "1_1") (pintype "passive"))
      (node (ref "C14") (pin "1") (pinfunction "1_1") (pintype "passive"))
      (node (ref "C15") (pin "1") (pinfunction "1_1") (pintype "passive"))
      (node (ref "C16") (pin "1") (pinfunction "1_1") (pintype "passive"))
      (node (ref "C17") (pin "1") (pinfunction "1_1") (pintype "passive"))
      (node (ref "C18") (pin "1") (pinfunction "1_1") (pintype "passive"))
      (node (ref "C19") (pin "1") (pinfunction "1_1") (pintype "passive"))
      (node (ref "C2") (pin "2") (pinfunction "2_2") (pintype "passive"))
      (node (ref "C3") (pin "1") (pinfunction "1_1") (pintype "passive"))
      (node (ref "C4") (pin "1") (pinfunction "1_1") (pintype "passive"))
      (node (ref "C5") (pin "1") (pinfunction "1_1") (pintype "passive"))
      (node (ref "C6") (pin "1") (pinfunction "1_1") (pintype "passive"))
      (node (ref "C7") (pin "1") (pinfunction "1_1") (pintype "passive"))
      (node (ref "C8") (pin "1") (pinfunction "1_1") (pintype "passive"))
      (node (ref "C9") (pin "1") (pinfunction "1_1") (pintype "passive"))
      (node (ref "D4") (pin "K") (pinfunction "K_K") (pintype "passive"))
      (node (ref "DDR1") (pin "1") (pinfunction "1_1") (pintype "passive"))
      (node (ref "DDR1") (pin "10") (pinfunction "10_10") (pintype "passive"))
      (node (ref "DDR1") (pin "11") (pinfunction "11_11") (pintype "passive"))
      (node (ref "DDR1") (pin "12") (pinfunction "12_12") (pintype "passive"))
      (node (ref "DDR1") (pin "13") (pinfunction "13_13") (pintype "passive"))
      (node (ref "DDR1") (pin "14") (pinfunction "14_14") (pintype "passive"))
      (node (ref "DDR1") (pin "15") (pinfunction "15_15") (pintype "passive"))
      (node (ref "DDR1") (pin "16") (pinfunction "16_16") (pintype "passive"))
      (node (ref "DDR1") (pin "17") (pinfunction "17_17") (pintype "passive"))
      (node (ref "DDR1") (pin "18") (pinfunction "18_18") (pintype "passive"))
      (node (ref "DDR1") (pin "19") (pinfunction "19_19") (pintype "passive"))
      (node (ref "DDR1") (pin "2") (pinfunction "2_2") (pintype "passive"))
      (node (ref "DDR1") (pin "20") (pinfunction "20_20") (pintype "passive"))
      (node (ref "DDR1") (pin "21") (pinfunction "21_21") (pintype "passive"))
      (node (ref "DDR1") (pin "22") (pinfunction "22_22") (pintype "passive"))
      (node (ref "DDR1") (pin "23") (pinfunction "23_23") (pintype "passive"))
      (node (ref "DDR1") (pin "24") (pinfunction "24_24") (pintype "passive"))
      (node (ref "DDR1") (pin "25") (pinfunction "25_25") (pintype "passive"))
      (node (ref "DDR1") (pin "26") (pinfunction "26_26") (pintype "passive"))
      (node (ref "DDR1") (pin "27") (pinfunction "27_27") (pintype "passive"))
      (node (ref "DDR1") (pin "28") (pinfunction "28_28") (pintype "passive"))
      (node (ref "DDR1") (pin "29") (pinfunction "29_29") (pintype "passive"))
      (node (ref "DDR1") (pin "3") (pinfunction "3_3") (pintype "passive"))
      (node (ref "DDR1") (pin "30") (pinfunction "30_30") (pintype "passive"))
      (node (ref "DDR1") (pin "31") (pinfunction "31_31") (pintype "passive"))
      (node (ref "DDR1") (pin "32") (pinfunction "32_32") (pintype "passive"))
      (node (ref "DDR1") (pin "33") (pinfunction "33_33") (pintype "passive"))
      (node (ref "DDR1") (pin "34") (pinfunction "34_34") (pintype "passive"))
      (node (ref "DDR1") (pin "35") (pinfunction "35_35") (pintype "passive"))
      (node (ref "DDR1") (pin "36") (pinfunction "36_36") (pintype "passive"))
      (node (ref "DDR1") (pin "4") (pinfunction "4_4") (pintype "passive"))
      (node (ref "DDR1") (pin "5") (pinfunction "5_5") (pintype "passive"))
      (node (ref "DDR1") (pin "6") (pinfunction "6_6") (pintype "passive"))
      (node (ref "DDR1") (pin "7") (pinfunction "7_7") (pintype "passive"))
      (node (ref "DDR1") (pin "8") (pinfunction "8_8") (pintype "passive"))
      (node (ref "DDR1") (pin "9") (pinfunction "9_9") (pintype "passive"))
      (node (ref "JP1") (pin "1") (pinfunction "1_1") (pintype "passive"))
      (node (ref "R2") (pin "2") (pinfunction "2_2") (pintype "passive"))
      (node (ref "R3") (pin "2") (pinfunction "2_2") (pintype "passive"))
      (node (ref "S1") (pin "2") (pinfunction "2_2") (pintype "passive"))
      (node (ref "U1") (pin "107") (pinfunction "VSS_107") (pintype "passive"))
      (node (ref "U1") (pin "120") (pinfunction "VSS_120") (pintype "passive"))
      (node (ref "U1") (pin "130") (pinfunction "VSS_130") (pintype "passive"))
      (node (ref "U1") (pin "143") (pinfunction "VSS_143") (pintype "passive"))
      (node (ref "U1") (pin "16") (pinfunction "VSS_16") (pintype "passive"))
      (node (ref "U1") (pin "30") (pinfunction "VSSA_30") (pintype "passive"))
      (node (ref "U1") (pin "31") (pinfunction "Vref-_31") (pintype "passive"))
      (node (ref "U1") (pin "38") (pinfunction "VSS_38") (pintype "passive"))
      (node (ref "U1") (pin "51") (pinfunction "VSS_51") (pintype "passive"))
      (node (ref "U1") (pin "61") (pinfunction "VSS_61") (pintype "passive"))
      (node (ref "U1") (pin "71") (pinfunction "VSS_71") (pintype "passive"))
      (node (ref "U1") (pin "83") (pinfunction "VSS_83") (pintype "passive"))
      (node (ref "U1") (pin "94") (pinfunction "VSS_94") (pintype "passive"))
      (node (ref "U2") (pin "4") (pinfunction "GND_4") (pintype "passive"))
      (node (ref "Y2") (pin "2") (pinfunction "2_2") (pintype "passive"))
      (node (ref "Y2") (pin "4") (pinfunction "4_4") (pintype "passive"))
    )
    (net (code "116") (name "Net-(D1-PadK)") (class "Default")
      (node (ref "D1") (pin "K") (pinfunction "K_K") (pintype "passive"))
      (node (ref "R2") (pin "1") (pinfunction "1_1") (pintype "passive"))
    )
    (net (code "117") (name "Net-(D2-PadK)") (class "Default")
      (node (ref "D2") (pin "K") (pinfunction "K_K") (pintype "passive"))
      (node (ref "R3") (pin "1") (pinfunction "1_1") (pintype "passive"))
    )
    (net (code "118") (name "Net-(D4-PadA)") (class "Default")
      (node (ref "D4") (pin "A") (pinfunction "A_A") (pintype "passive"))
      (node (ref "R19") (pin "2") (pinfunction "2_2") (pintype "passive"))
    )
    (net (code "119") (name "Net-(U1-OSC_IN)") (class "Default")
      (node (ref "C5") (pin "2") (pinfunction "2_2") (pintype "passive"))
      (node (ref "R4") (pin "1") (pinfunction "1_1") (pintype "passive"))
      (node (ref "U1") (pin "23") (pinfunction "OSC_IN_23") (pintype "passive"))
      (node (ref "Y2") (pin "3") (pinfunction "3_3") (pintype "passive"))
    )
    (net (code "120") (name "Net-(U1-OSC_OUT)") (class "Default")
      (node (ref "C6") (pin "2") (pinfunction "2_2") (pintype "passive"))
      (node (ref "R4") (pin "2") (pinfunction "2_2") (pintype "passive"))
      (node (ref "U1") (pin "24") (pinfunction "OSC_OUT_24") (pintype "passive"))
      (node (ref "Y2") (pin "1") (pinfunction "1_1") (pintype "passive"))
    )
    (net (code "121") (name "Net-(U1-PC14-OSC32_IN)") (class "Default")
      (node (ref "C3") (pin "2") (pinfunction "2_2") (pintype "passive"))
      (node (ref "U1") (pin "8") (pinfunction "PC14-OSC32_IN_8") (pintype "passive"))
      (node (ref "Y1") (pin "1") (pinfunction "1_1") (pintype "passive"))
    )
    (net (code "122") (name "Net-(U1-PC15-OSC32_OUT)") (class "Default")
      (node (ref "C4") (pin "2") (pinfunction "2_2") (pintype "passive"))
      (node (ref "U1") (pin "9") (pinfunction "PC15-OSC32_OUT_9") (pintype "passive"))
      (node (ref "Y1") (pin "2") (pinfunction "2_2") (pintype "passive"))
    )
    (net (code "123") (name "Net-(U1-VDDA)") (class "Default")
      (node (ref "C7") (pin "2") (pinfunction "2_2") (pintype "passive"))
      (node (ref "C8") (pin "2") (pinfunction "2_2") (pintype "passive"))
      (node (ref "R5") (pin "1") (pinfunction "1_1") (pintype "passive"))
      (node (ref "U1") (pin "32") (pinfunction "Vref+_32") (pintype "passive"))
      (node (ref "U1") (pin "33") (pinfunction "VDDA_33") (pintype "passive"))
    )
    (net (code "124") (name "unconnected-(DDR1-Pad73)") (class "Default")
      (node (ref "DDR1") (pin "73") (pinfunction "73_73") (pintype "passive"))
    )
    (net (code "125") (name "unconnected-(DDR1-Pad74)") (class "Default")
      (node (ref "DDR1") (pin "74") (pinfunction "74_74") (pintype "passive"))
    )
    (net (code "126") (name "unconnected-(DDR1-Pad75)") (class "Default")
      (node (ref "DDR1") (pin "75") (pinfunction "75_75") (pintype "passive"))
    )
    (net (code "127") (name "unconnected-(DDR1-Pad76)") (class "Default")
      (node (ref "DDR1") (pin "76") (pinfunction "76_76") (pintype "passive"))
    )
    (net (code "128") (name "unconnected-(DDR1-Pad77)") (class "Default")
      (node (ref "DDR1") (pin "77") (pinfunction "77_77") (pintype "passive"))
    )
    (net (code "129") (name "unconnected-(DDR1-Pad78)") (class "Default")
      (node (ref "DDR1") (pin "78") (pinfunction "78_78") (pintype "passive"))
    )
    (net (code "130") (name "unconnected-(DDR1-Pad79)") (class "Default")
      (node (ref "DDR1") (pin "79") (pinfunction "79_79") (pintype "passive"))
    )
    (net (code "131") (name "unconnected-(DDR1-Pad80)") (class "Default")
      (node (ref "DDR1") (pin "80") (pinfunction "80_80") (pintype "passive"))
    )
    (net (code "132") (name "unconnected-(DDR1-Pad81)") (class "Default")
      (node (ref "DDR1") (pin "81") (pinfunction "81_81") (pintype "passive"))
    )
    (net (code "133") (name "unconnected-(DDR1-Pad82)") (class "Default")
      (node (ref "DDR1") (pin "82") (pinfunction "82_82") (pintype "passive"))
    )
    (net (code "134") (name "unconnected-(DDR1-Pad83)") (class "Default")
      (node (ref "DDR1") (pin "83") (pinfunction "83_83") (pintype "passive"))
    )
    (net (code "135") (name "unconnected-(DDR1-Pad84)") (class "Default")
      (node (ref "DDR1") (pin "84") (pinfunction "84_84") (pintype "passive"))
    )
    (net (code "136") (name "unconnected-(DDR1-Pad85)") (class "Default")
      (node (ref "DDR1") (pin "85") (pinfunction "85_85") (pintype "passive"))
    )
    (net (code "137") (name "unconnected-(DDR1-Pad86)") (class "Default")
      (node (ref "DDR1") (pin "86") (pinfunction "86_86") (pintype "passive"))
    )
    (net (code "138") (name "unconnected-(DDR1-Pad87)") (class "Default")
      (node (ref "DDR1") (pin "87") (pinfunction "87_87") (pintype "passive"))
    )
    (net (code "139") (name "unconnected-(DDR1-Pad88)") (class "Default")
      (node (ref "DDR1") (pin "88") (pinfunction "88_88") (pintype "passive"))
    )
    (net (code "140") (name "unconnected-(DDR1-Pad89)") (class "Default")
      (node (ref "DDR1") (pin "89") (pinfunction "89_89") (pintype "passive"))
    )
    (net (code "141") (name "unconnected-(DDR1-Pad90)") (class "Default")
      (node (ref "DDR1") (pin "90") (pinfunction "90_90") (pintype "passive"))
    )
    (net (code "142") (name "unconnected-(DDR1-Pad91)") (class "Default")
      (node (ref "DDR1") (pin "91") (pinfunction "91_91") (pintype "passive"))
    )
    (net (code "143") (name "unconnected-(DDR1-Pad92)") (class "Default")
      (node (ref "DDR1") (pin "92") (pinfunction "92_92") (pintype "passive"))
    )
    (net (code "144") (name "unconnected-(DDR1-Pad93)") (class "Default")
      (node (ref "DDR1") (pin "93") (pinfunction "93_93") (pintype "passive"))
    )
    (net (code "145") (name "unconnected-(DDR1-Pad94)") (class "Default")
      (node (ref "DDR1") (pin "94") (pinfunction "94_94") (pintype "passive"))
    )
    (net (code "146") (name "unconnected-(DDR1-Pad95)") (class "Default")
      (node (ref "DDR1") (pin "95") (pinfunction "95_95") (pintype "passive"))
    )
    (net (code "147") (name "unconnected-(DDR1-Pad96)") (class "Default")
      (node (ref "DDR1") (pin "96") (pinfunction "96_96") (pintype "passive"))
    )
    (net (code "148") (name "unconnected-(U1-NC-Pad106)") (class "Default")
      (node (ref "U1") (pin "106") (pinfunction "NC_106") (pintype "passive"))
    )
  )
)
